# other.net
KiCad netlist of a schematic drawn in Altium Designer
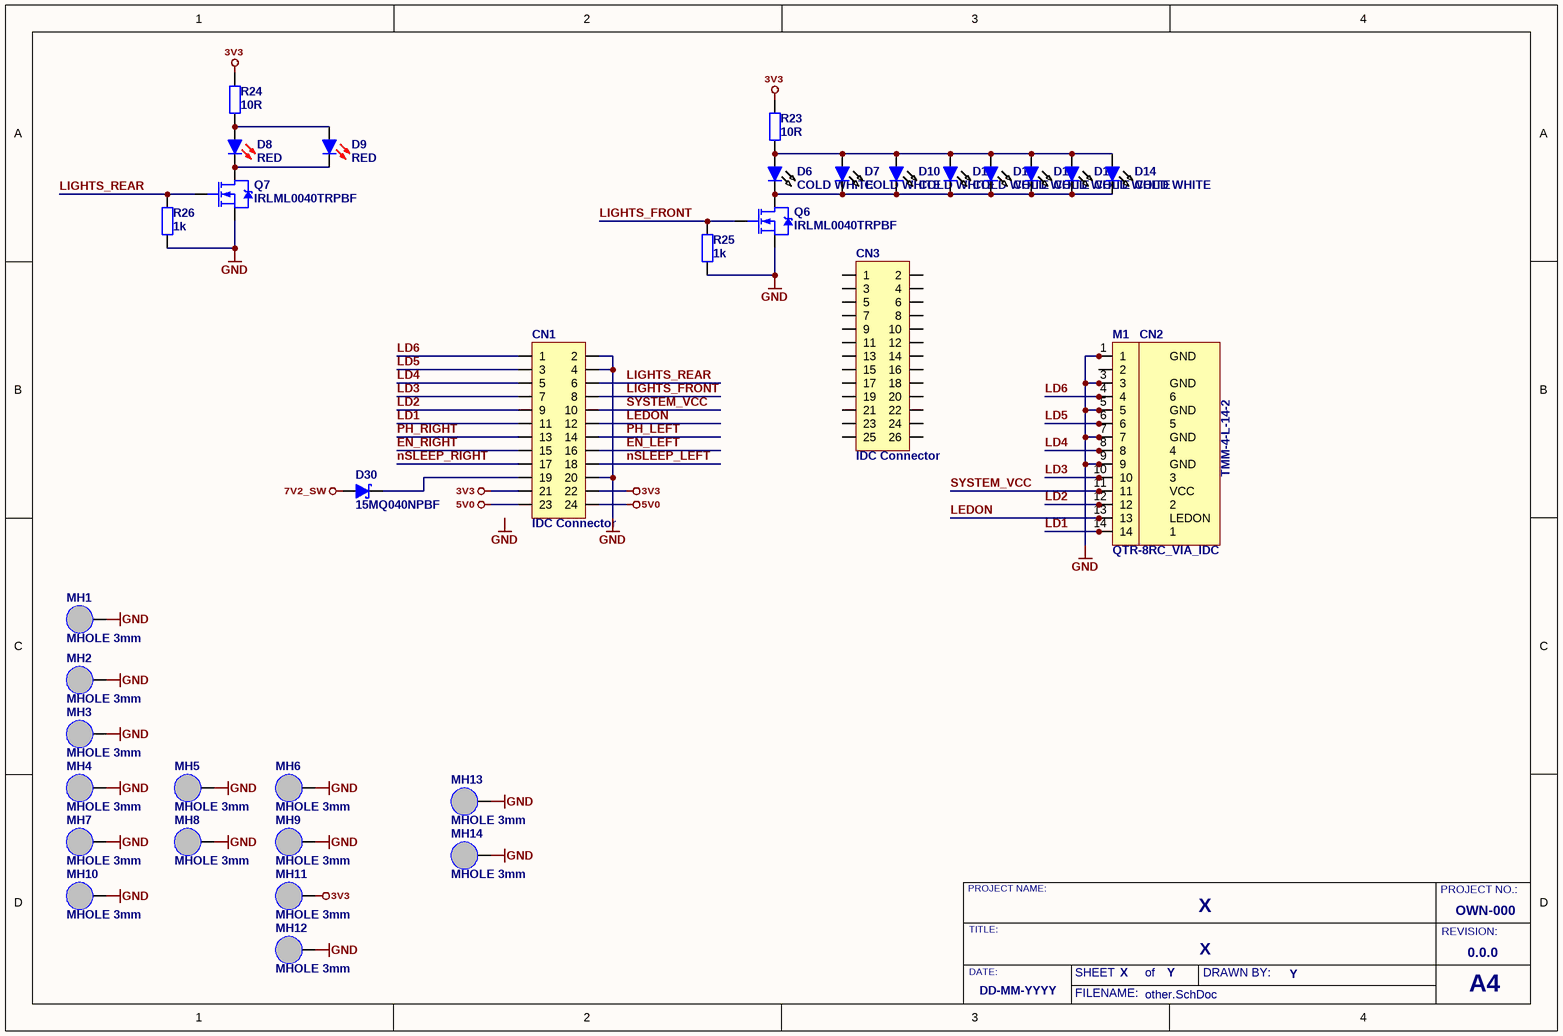
[diagram p0: other.SchDoc]

(export (version "E")
  (design (tool "Eeschema 10.0.6"))
  (components
    (comp (ref "CN1")
      (value "IDC Connector")
      (footprint "IDC24_RA _W_CN")
      (libsource (lib "idc") (part "CN_12x2"))
    )
    (comp (ref "CN2")
      (value "TMM-4-L-14-2")
      (footprint "MM_14_LCK_W_CN")
      (description "14-pin MicroMarch Female Socket With Locking Mechanism, Vertical, THT")
      (libsource (lib "micromatch") (part "TMM-4-L-14-2"))
    )
    (comp (ref "CN3") (value "IDC Connector") (footprint "IDC26_RA") (libsource (lib "idc") (part "CN_13x2")))
    (comp (ref "D6")
      (value "COLD WHITE")
      (footprint "LTW-108DCG-HS10")
      (description "LTW-108DCG-HS10")
      (libsource (lib "leds") (part "LTW-108DCG-HS10"))
    )
    (comp (ref "D7")
      (value "COLD WHITE")
      (footprint "LTW-108DCG-HS10")
      (description "LTW-108DCG-HS10")
      (libsource (lib "leds") (part "LTW-108DCG-HS10"))
    )
    (comp (ref "D8")
      (value "RED")
      (footprint "FIX-LED1L-2.5")
      (description "Throughole RED LED")
      (libsource (lib "leds") (part "LED_THT_RED"))
    )
    (comp (ref "D9")
      (value "RED")
      (footprint "FIX-LED1L-2.5")
      (description "Throughole RED LED")
      (libsource (lib "leds") (part "LED_THT_RED"))
    )
    (comp (ref "D10")
      (value "COLD WHITE")
      (footprint "LTW-108DCG-HS10")
      (description "LTW-108DCG-HS10")
      (libsource (lib "leds") (part "LTW-108DCG-HS10"))
    )
    (comp (ref "D11")
      (value "COLD WHITE")
      (footprint "LTW-108DCG-HS10")
      (description "LTW-108DCG-HS10")
      (libsource (lib "leds") (part "LTW-108DCG-HS10"))
    )
    (comp (ref "D12")
      (value "COLD WHITE")
      (footprint "LTW-108DCG-HS10")
      (description "LTW-108DCG-HS10")
      (libsource (lib "leds") (part "LTW-108DCG-HS10"))
    )
    (comp (ref "D13")
      (value "COLD WHITE")
      (footprint "LTW-108DCG-HS10")
      (description "LTW-108DCG-HS10")
      (libsource (lib "leds") (part "LTW-108DCG-HS10"))
    )
    (comp (ref "D14")
      (value "COLD WHITE")
      (footprint "LTW-108DCG-HS10")
      (description "LTW-108DCG-HS10")
      (libsource (lib "leds") (part "LTW-108DCG-HS10"))
    )
    (comp (ref "D15")
      (value "COLD WHITE")
      (footprint "LTW-108DCG-HS10")
      (description "LTW-108DCG-HS10")
      (libsource (lib "leds") (part "LTW-108DCG-HS10"))
    )
    (comp (ref "D30")
      (value "15MQ040NPBF")
      (footprint "SMA")
      (description "Schottky barrier rectifier: 40V, 1.5A, SMA")
      (libsource (lib "diodes_schottky") (part "15MQ040NPBF"))
    )
    (comp (ref "M1")
      (value "QTR-8RC_VIA_IDC")
      (footprint "QTR-8RC_SNAPPED_IDC_2")
      (description "QTR-8RC Reflectance Sensor Array (Pololu item No. 961)")
      (libsource (lib "other_modules") (part "QTR-8RC_VIA_IDC"))
    )
    (comp (ref "MH1")
      (value "MHOLE 3mm")
      (footprint "3mm screw drill I")
      (description "3mm Mounting Hole")
      (libsource (lib "mechanical_other") (part "MHOLE_3MM"))
    )
    (comp (ref "MH2")
      (value "MHOLE 3mm")
      (footprint "3mm screw drill I")
      (description "3mm Mounting Hole")
      (libsource (lib "mechanical_other") (part "MHOLE_3MM"))
    )
    (comp (ref "MH3")
      (value "MHOLE 3mm")
      (footprint "3mm screw drill I")
      (description "3mm Mounting Hole")
      (libsource (lib "mechanical_other") (part "MHOLE_3MM"))
    )
    (comp (ref "MH4")
      (value "MHOLE 3mm")
      (footprint "3mm screw drill I")
      (description "3mm Mounting Hole")
      (libsource (lib "mechanical_other") (part "MHOLE_3MM"))
    )
    (comp (ref "MH5")
      (value "MHOLE 3mm")
      (footprint "3mm screw drill I")
      (description "3mm Mounting Hole")
      (libsource (lib "mechanical_other") (part "MHOLE_3MM"))
    )
    (comp (ref "MH6")
      (value "MHOLE 3mm")
      (footprint "3mm screw drill I")
      (description "3mm Mounting Hole")
      (libsource (lib "mechanical_other") (part "MHOLE_3MM"))
    )
    (comp (ref "MH7")
      (value "MHOLE 3mm")
      (footprint "3mm screw drill I")
      (description "3mm Mounting Hole")
      (libsource (lib "mechanical_other") (part "MHOLE_3MM"))
    )
    (comp (ref "MH8")
      (value "MHOLE 3mm")
      (footprint "3mm screw drill I")
      (description "3mm Mounting Hole")
      (libsource (lib "mechanical_other") (part "MHOLE_3MM"))
    )
    (comp (ref "MH9")
      (value "MHOLE 3mm")
      (footprint "3mm screw drill I")
      (description "3mm Mounting Hole")
      (libsource (lib "mechanical_other") (part "MHOLE_3MM"))
    )
    (comp (ref "MH10")
      (value "MHOLE 3mm")
      (footprint "3mm screw drill I")
      (description "3mm Mounting Hole")
      (libsource (lib "mechanical_other") (part "MHOLE_3MM"))
    )
    (comp (ref "MH11")
      (value "MHOLE 3mm")
      (footprint "3mm screw drill I")
      (description "3mm Mounting Hole")
      (libsource (lib "mechanical_other") (part "MHOLE_3MM"))
    )
    (comp (ref "MH12")
      (value "MHOLE 3mm")
      (footprint "3mm screw drill I")
      (description "3mm Mounting Hole")
      (libsource (lib "mechanical_other") (part "MHOLE_3MM"))
    )
    (comp (ref "MH13")
      (value "MHOLE 3mm")
      (footprint "3mm screw drill I")
      (description "3mm Mounting Hole")
      (libsource (lib "mechanical_other") (part "MHOLE_3MM"))
    )
    (comp (ref "MH14")
      (value "MHOLE 3mm")
      (footprint "3mm screw drill I")
      (description "3mm Mounting Hole")
      (libsource (lib "mechanical_other") (part "MHOLE_3MM"))
    )
    (comp (ref "Q6")
      (value "IRLML0040TRPBF")
      (footprint "SOT-23")
      (description "N-Channel; 40V, 3.6A, 1,25W; HEXFET Power MOS-FET")
      (libsource (lib "transistors_mos") (part "IRLML0040TRPBF"))
    )
    (comp (ref "Q7")
      (value "IRLML0040TRPBF")
      (footprint "SOT-23")
      (description "N-Channel; 40V, 3.6A, 1,25W; HEXFET Power MOS-FET")
      (libsource (lib "transistors_mos") (part "IRLML0040TRPBF"))
    )
    (comp (ref "R23")
      (value "10R")
      (footprint "R0805")
      (description "Resistor")
      (libsource (lib "resistors") (part "Res"))
    )
    (comp (ref "R24")
      (value "10R")
      (footprint "R0805")
      (description "Resistor")
      (libsource (lib "resistors") (part "Res"))
    )
    (comp (ref "R25")
      (value "1k")
      (footprint "R0805")
      (description "Resistor")
      (libsource (lib "resistors") (part "Res"))
    )
    (comp (ref "R26")
      (value "1k")
      (footprint "R0805")
      (description "Resistor")
      (libsource (lib "resistors") (part "Res"))
    )
  )
  (nets
    (net (code "1") (name "/EN_LEFT") (class "Default")
      (node (ref "CN1") (pin "16") (pinfunction "16_16") (pintype "passive"))
    )
    (net (code "2") (name "/EN_RIGHT") (class "Default")
      (node (ref "CN1") (pin "15") (pinfunction "15_15") (pintype "passive"))
    )
    (net (code "3") (name "/LD1") (class "Default")
      (node (ref "CN1") (pin "11") (pinfunction "11_11") (pintype "passive"))
      (node (ref "CN2") (pin "14") (pinfunction "14_14") (pintype "passive"))
      (node (ref "M1") (pin "14") (pinfunction "1_14") (pintype "passive"))
    )
    (net (code "4") (name "/LD2") (class "Default")
      (node (ref "CN1") (pin "9") (pinfunction "9_9") (pintype "passive"))
      (node (ref "CN2") (pin "12") (pinfunction "12_12") (pintype "passive"))
      (node (ref "M1") (pin "12") (pinfunction "2_12") (pintype "passive"))
    )
    (net (code "5") (name "/LD3") (class "Default")
      (node (ref "CN1") (pin "7") (pinfunction "7_7") (pintype "passive"))
      (node (ref "CN2") (pin "10") (pinfunction "10_10") (pintype "passive"))
      (node (ref "M1") (pin "10") (pinfunction "3_10") (pintype "passive"))
    )
    (net (code "6") (name "/LD4") (class "Default")
      (node (ref "CN1") (pin "5") (pinfunction "5_5") (pintype "passive"))
      (node (ref "CN2") (pin "8") (pinfunction "8_8") (pintype "passive"))
      (node (ref "M1") (pin "8") (pinfunction "4_8") (pintype "passive"))
    )
    (net (code "7") (name "/LD5") (class "Default")
      (node (ref "CN1") (pin "3") (pinfunction "3_3") (pintype "passive"))
      (node (ref "CN2") (pin "6") (pinfunction "6_6") (pintype "passive"))
      (node (ref "M1") (pin "6") (pinfunction "5_6") (pintype "passive"))
    )
    (net (code "8") (name "/LD6") (class "Default")
      (node (ref "CN1") (pin "1") (pinfunction "1_1") (pintype "passive"))
      (node (ref "CN2") (pin "4") (pinfunction "4_4") (pintype "passive"))
      (node (ref "M1") (pin "4") (pinfunction "6_4") (pintype "passive"))
    )
    (net (code "9") (name "/LEDON") (class "Default")
      (node (ref "CN1") (pin "12") (pinfunction "12_12") (pintype "passive"))
      (node (ref "CN2") (pin "13") (pinfunction "13_13") (pintype "passive"))
      (node (ref "M1") (pin "13") (pinfunction "LEDON_13") (pintype "passive"))
    )
    (net (code "10") (name "/LIGHTS_FRONT") (class "Default")
      (node (ref "CN1") (pin "8") (pinfunction "8_8") (pintype "passive"))
      (node (ref "Q6") (pin "1") (pinfunction "G_1") (pintype "passive"))
      (node (ref "R25") (pin "1") (pinfunction "1_1") (pintype "passive"))
    )
    (net (code "11") (name "/LIGHTS_REAR") (class "Default")
      (node (ref "CN1") (pin "6") (pinfunction "6_6") (pintype "passive"))
      (node (ref "Q7") (pin "1") (pinfunction "G_1") (pintype "passive"))
      (node (ref "R26") (pin "1") (pinfunction "1_1") (pintype "passive"))
    )
    (net (code "12") (name "/PH_LEFT") (class "Default")
      (node (ref "CN1") (pin "14") (pinfunction "14_14") (pintype "passive"))
    )
    (net (code "13") (name "/PH_RIGHT") (class "Default")
      (node (ref "CN1") (pin "13") (pinfunction "13_13") (pintype "passive"))
    )
    (net (code "14") (name "/SYSTEM_VCC") (class "Default")
      (node (ref "CN1") (pin "10") (pinfunction "10_10") (pintype "passive"))
      (node (ref "CN2") (pin "11") (pinfunction "11_11") (pintype "passive"))
      (node (ref "M1") (pin "11") (pinfunction "VCC_11") (pintype "passive"))
    )
    (net (code "15") (name "/nSLEEP_LEFT") (class "Default")
      (node (ref "CN1") (pin "18") (pinfunction "18_18") (pintype "passive"))
    )
    (net (code "16") (name "/nSLEEP_RIGHT") (class "Default")
      (node (ref "CN1") (pin "17") (pinfunction "17_17") (pintype "passive"))
    )
    (net (code "17") (name "3V3") (class "Default")
      (node (ref "CN1") (pin "21") (pinfunction "21_21") (pintype "passive"))
      (node (ref "CN1") (pin "22") (pinfunction "22_22") (pintype "passive"))
      (node (ref "MH11") (pin "1") (pinfunction "GND_1") (pintype "passive"))
      (node (ref "R23") (pin "1") (pinfunction "1_1") (pintype "passive"))
      (node (ref "R24") (pin "1") (pinfunction "1_1") (pintype "passive"))
    )
    (net (code "18") (name "5V0") (class "Default")
      (node (ref "CN1") (pin "23") (pinfunction "23_23") (pintype "passive"))
      (node (ref "CN1") (pin "24") (pinfunction "24_24") (pintype "passive"))
    )
    (net (code "19") (name "7V2_SW") (class "Default")
      (node (ref "D30") (pin "1") (pinfunction "A_1") (pintype "passive"))
    )
    (net (code "20") (name "GND") (class "Default")
      (node (ref "CN1") (pin "2") (pinfunction "2_2") (pintype "passive"))
      (node (ref "CN1") (pin "20") (pinfunction "20_20") (pintype "passive"))
      (node (ref "CN1") (pin "4") (pinfunction "4_4") (pintype "passive"))
      (node (ref "CN2") (pin "1") (pinfunction "1_1") (pintype "passive"))
      (node (ref "CN2") (pin "3") (pinfunction "3_3") (pintype "passive"))
      (node (ref "CN2") (pin "5") (pinfunction "5_5") (pintype "passive"))
      (node (ref "CN2") (pin "7") (pinfunction "7_7") (pintype "passive"))
      (node (ref "CN2") (pin "9") (pinfunction "9_9") (pintype "passive"))
      (node (ref "M1") (pin "1") (pinfunction "GND_1") (pintype "passive"))
      (node (ref "M1") (pin "3") (pinfunction "GND_3") (pintype "passive"))
      (node (ref "M1") (pin "5") (pinfunction "GND_5") (pintype "passive"))
      (node (ref "M1") (pin "7") (pinfunction "GND_7") (pintype "passive"))
      (node (ref "M1") (pin "9") (pinfunction "GND_9") (pintype "passive"))
      (node (ref "MH1") (pin "1") (pinfunction "GND_1") (pintype "passive"))
      (node (ref "MH10") (pin "1") (pinfunction "GND_1") (pintype "passive"))
      (node (ref "MH12") (pin "1") (pinfunction "GND_1") (pintype "passive"))
      (node (ref "MH13") (pin "1") (pinfunction "GND_1") (pintype "passive"))
      (node (ref "MH14") (pin "1") (pinfunction "GND_1") (pintype "passive"))
      (node (ref "MH2") (pin "1") (pinfunction "GND_1") (pintype "passive"))
      (node (ref "MH3") (pin "1") (pinfunction "GND_1") (pintype "passive"))
      (node (ref "MH4") (pin "1") (pinfunction "GND_1") (pintype "passive"))
      (node (ref "MH5") (pin "1") (pinfunction "GND_1") (pintype "passive"))
      (node (ref "MH6") (pin "1") (pinfunction "GND_1") (pintype "passive"))
      (node (ref "MH7") (pin "1") (pinfunction "GND_1") (pintype "passive"))
      (node (ref "MH8") (pin "1") (pinfunction "GND_1") (pintype "passive"))
      (node (ref "MH9") (pin "1") (pinfunction "GND_1") (pintype "passive"))
      (node (ref "Q6") (pin "2") (pinfunction "S_2") (pintype "passive"))
      (node (ref "Q7") (pin "2") (pinfunction "S_2") (pintype "passive"))
      (node (ref "R25") (pin "2") (pinfunction "2_2") (pintype "passive"))
      (node (ref "R26") (pin "2") (pinfunction "2_2") (pintype "passive"))
    )
    (net (code "21") (name "Net-(D8-A)") (class "Default")
      (node (ref "D8") (pin "1") (pinfunction "A_1") (pintype "passive"))
      (node (ref "D9") (pin "1") (pinfunction "A_1") (pintype "passive"))
      (node (ref "R24") (pin "2") (pinfunction "2_2") (pintype "passive"))
    )
    (net (code "22") (name "Net-(D8-K)") (class "Default")
      (node (ref "D8") (pin "2") (pinfunction "K_2") (pintype "passive"))
      (node (ref "D9") (pin "2") (pinfunction "K_2") (pintype "passive"))
      (node (ref "Q7") (pin "3") (pinfunction "D_3") (pintype "passive"))
    )
    (net (code "23") (name "Net-(D10-A)") (class "Default")
      (node (ref "D10") (pin "1") (pinfunction "A_1") (pintype "passive"))
      (node (ref "D11") (pin "1") (pinfunction "A_1") (pintype "passive"))
      (node (ref "D12") (pin "1") (pinfunction "A_1") (pintype "passive"))
      (node (ref "D13") (pin "1") (pinfunction "A_1") (pintype "passive"))
      (node (ref "D14") (pin "1") (pinfunction "A_1") (pintype "passive"))
      (node (ref "D15") (pin "1") (pinfunction "A_1") (pintype "passive"))
      (node (ref "D6") (pin "1") (pinfunction "A_1") (pintype "passive"))
      (node (ref "D7") (pin "1") (pinfunction "A_1") (pintype "passive"))
      (node (ref "R23") (pin "2") (pinfunction "2_2") (pintype "passive"))
    )
    (net (code "24") (name "Net-(D10-K)") (class "Default")
      (node (ref "D10") (pin "2") (pinfunction "K_2") (pintype "passive"))
      (node (ref "D11") (pin "2") (pinfunction "K_2") (pintype "passive"))
      (node (ref "D12") (pin "2") (pinfunction "K_2") (pintype "passive"))
      (node (ref "D13") (pin "2") (pinfunction "K_2") (pintype "passive"))
      (node (ref "D14") (pin "2") (pinfunction "K_2") (pintype "passive"))
      (node (ref "D15") (pin "2") (pinfunction "K_2") (pintype "passive"))
      (node (ref "D6") (pin "2") (pinfunction "K_2") (pintype "passive"))
      (node (ref "D7") (pin "2") (pinfunction "K_2") (pintype "passive"))
      (node (ref "Q6") (pin "3") (pinfunction "D_3") (pintype "passive"))
    )
    (net (code "25") (name "Net-(D30-K)") (class "Default")
      (node (ref "CN1") (pin "19") (pinfunction "19_19") (pintype "passive"))
      (node (ref "D30") (pin "2") (pinfunction "K_2") (pintype "passive"))
    )
    (net (code "26") (name "unconnected-(CN2-Pad2)") (class "Default")
      (node (ref "CN2") (pin "2") (pinfunction "2_2") (pintype "passive"))
    )
    (net (code "27") (name "unconnected-(CN3-Pad1)") (class "Default")
      (node (ref "CN3") (pin "1") (pinfunction "1_1") (pintype "passive"))
    )
    (net (code "28") (name "unconnected-(CN3-Pad2)") (class "Default")
      (node (ref "CN3") (pin "2") (pinfunction "2_2") (pintype "passive"))
    )
    (net (code "29") (name "unconnected-(CN3-Pad3)") (class "Default")
      (node (ref "CN3") (pin "3") (pinfunction "3_3") (pintype "passive"))
    )
    (net (code "30") (name "unconnected-(CN3-Pad4)") (class "Default")
      (node (ref "CN3") (pin "4") (pinfunction "4_4") (pintype "passive"))
    )
    (net (code "31") (name "unconnected-(CN3-Pad5)") (class "Default")
      (node (ref "CN3") (pin "5") (pinfunction "5_5") (pintype "passive"))
    )
    (net (code "32") (name "unconnected-(CN3-Pad6)") (class "Default")
      (node (ref "CN3") (pin "6") (pinfunction "6_6") (pintype "passive"))
    )
    (net (code "33") (name "unconnected-(CN3-Pad7)") (class "Default")
      (node (ref "CN3") (pin "7") (pinfunction "7_7") (pintype "passive"))
    )
    (net (code "34") (name "unconnected-(CN3-Pad8)") (class "Default")
      (node (ref "CN3") (pin "8") (pinfunction "8_8") (pintype "passive"))
    )
    (net (code "35") (name "unconnected-(CN3-Pad9)") (class "Default")
      (node (ref "CN3") (pin "9") (pinfunction "9_9") (pintype "passive"))
    )
    (net (code "36") (name "unconnected-(CN3-Pad10)") (class "Default")
      (node (ref "CN3") (pin "10") (pinfunction "10_10") (pintype "passive"))
    )
    (net (code "37") (name "unconnected-(CN3-Pad11)") (class "Default")
      (node (ref "CN3") (pin "11") (pinfunction "11_11") (pintype "passive"))
    )
    (net (code "38") (name "unconnected-(CN3-Pad12)") (class "Default")
      (node (ref "CN3") (pin "12") (pinfunction "12_12") (pintype "passive"))
    )
    (net (code "39") (name "unconnected-(CN3-Pad13)") (class "Default")
      (node (ref "CN3") (pin "13") (pinfunction "13_13") (pintype "passive"))
    )
    (net (code "40") (name "unconnected-(CN3-Pad14)") (class "Default")
      (node (ref "CN3") (pin "14") (pinfunction "14_14") (pintype "passive"))
    )
    (net (code "41") (name "unconnected-(CN3-Pad15)") (class "Default")
      (node (ref "CN3") (pin "15") (pinfunction "15_15") (pintype "passive"))
    )
    (net (code "42") (name "unconnected-(CN3-Pad16)") (class "Default")
      (node (ref "CN3") (pin "16") (pinfunction "16_16") (pintype "passive"))
    )
    (net (code "43") (name "unconnected-(CN3-Pad17)") (class "Default")
      (node (ref "CN3") (pin "17") (pinfunction "17_17") (pintype "passive"))
    )
    (net (code "44") (name "unconnected-(CN3-Pad18)") (class "Default")
      (node (ref "CN3") (pin "18") (pinfunction "18_18") (pintype "passive"))
    )
    (net (code "45") (name "unconnected-(CN3-Pad19)") (class "Default")
      (node (ref "CN3") (pin "19") (pinfunction "19_19") (pintype "passive"))
    )
    (net (code "46") (name "unconnected-(CN3-Pad20)") (class "Default")
      (node (ref "CN3") (pin "20") (pinfunction "20_20") (pintype "passive"))
    )
    (net (code "47") (name "unconnected-(CN3-Pad21)") (class "Default")
      (node (ref "CN3") (pin "21") (pinfunction "21_21") (pintype "passive"))
    )
    (net (code "48") (name "unconnected-(CN3-Pad22)") (class "Default")
      (node (ref "CN3") (pin "22") (pinfunction "22_22") (pintype "passive"))
    )
    (net (code "49") (name "unconnected-(CN3-Pad23)") (class "Default")
      (node (ref "CN3") (pin "23") (pinfunction "23_23") (pintype "passive"))
    )
    (net (code "50") (name "unconnected-(CN3-Pad24)") (class "Default")
      (node (ref "CN3") (pin "24") (pinfunction "24_24") (pintype "passive"))
    )
    (net (code "51") (name "unconnected-(CN3-Pad25)") (class "Default")
      (node (ref "CN3") (pin "25") (pinfunction "25_25") (pintype "passive"))
    )
    (net (code "52") (name "unconnected-(CN3-Pad26)") (class "Default")
      (node (ref "CN3") (pin "26") (pinfunction "26_26") (pintype "passive"))
    )
  )
)
